# Tiny_Programmer_v10.net
KiCad netlist of a schematic drawn in EAGLE
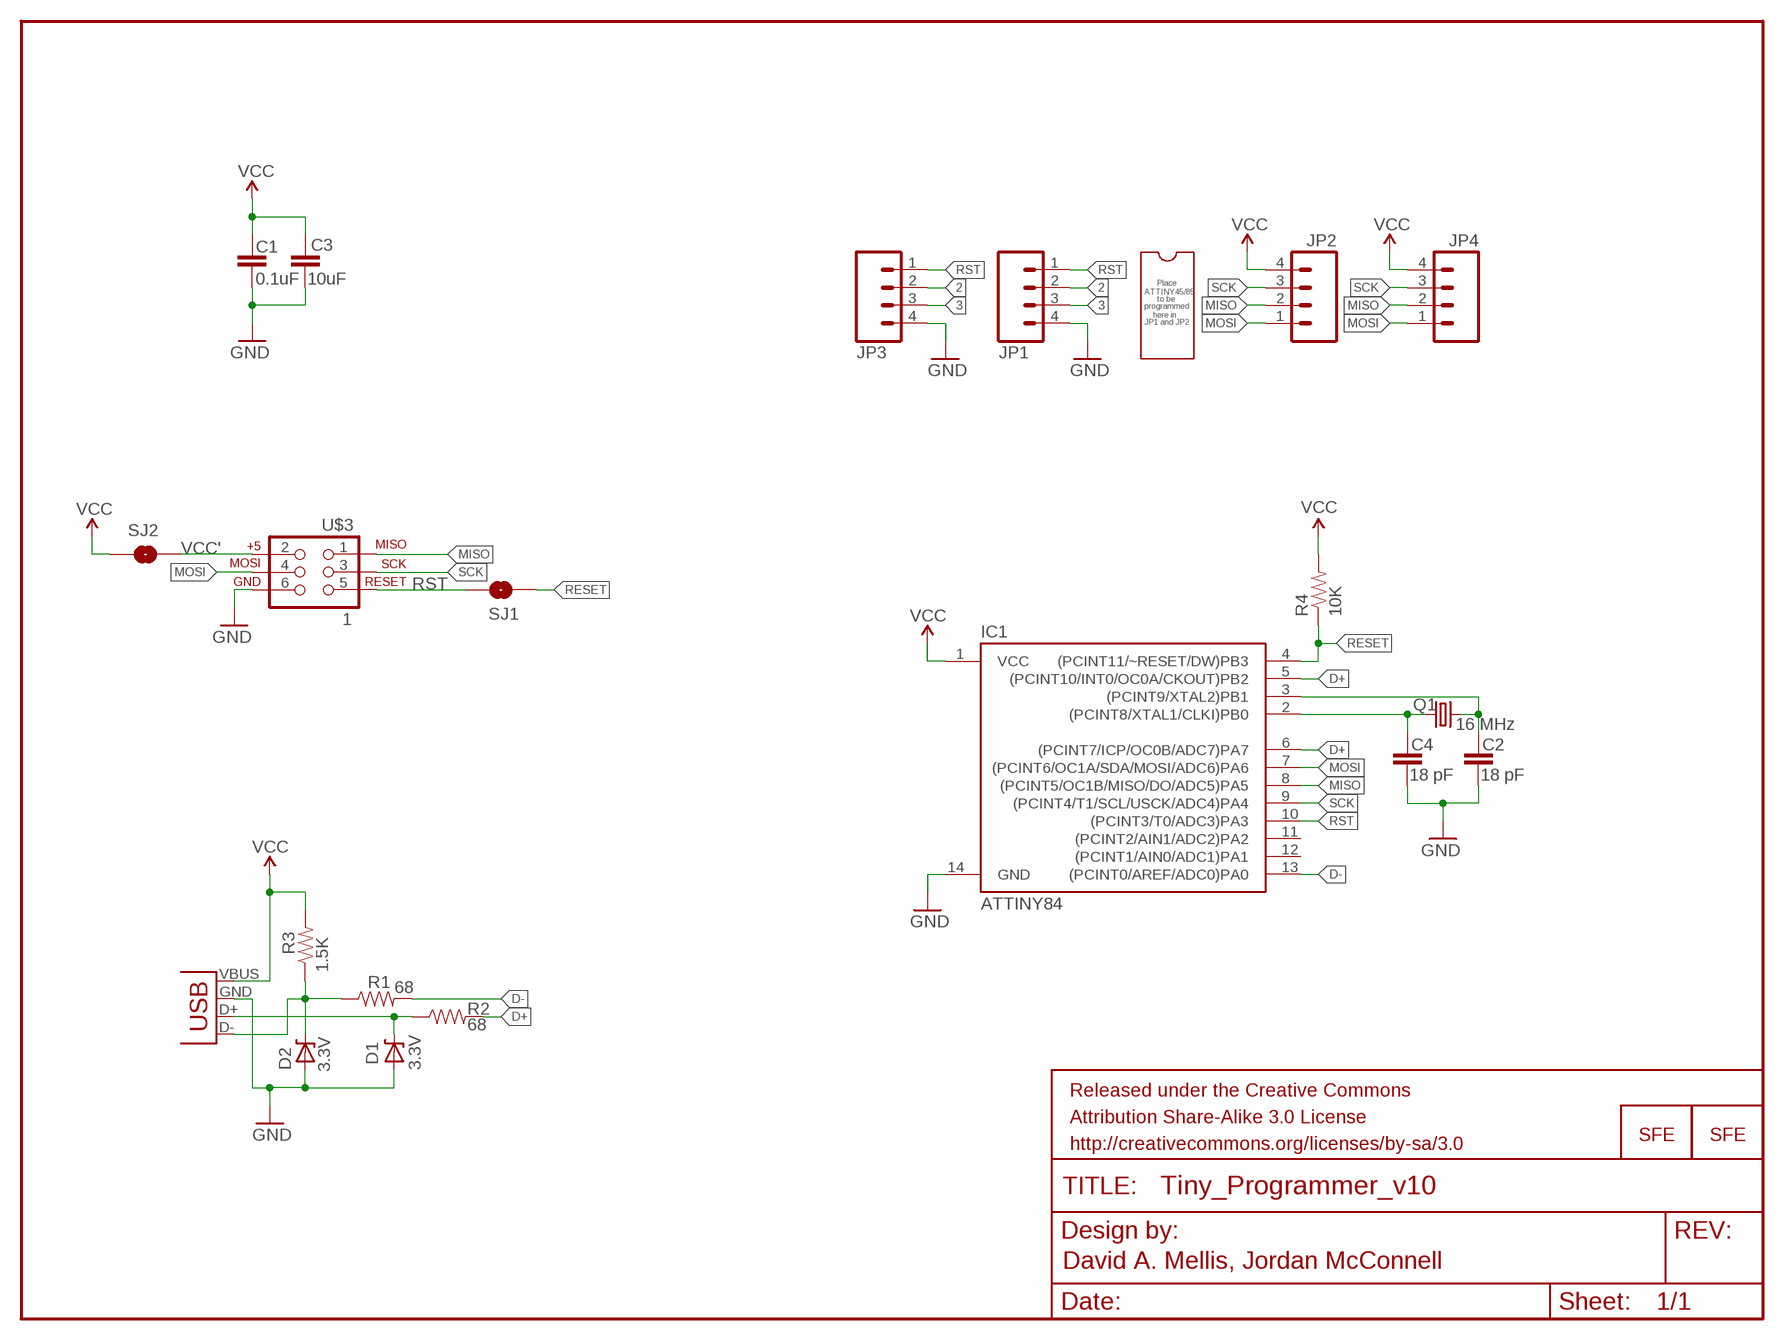
[diagram p0: schematic, sheet 1]

(export (version "E")
  (design (tool "Eeschema 10.0.6"))
  (components
    (comp (ref "C1")
      (value "0.1uF")
      (footprint "eagle-import:0402-CAP")
      (libsource (lib "eagle-import") (part "CAP0402-CAP"))
    )
    (comp (ref "C2")
      (value "18 pF")
      (footprint "eagle-import:0402-CAP")
      (libsource (lib "eagle-import") (part "CAP0402-CAP"))
    )
    (comp (ref "C3")
      (value "10uF")
      (footprint "eagle-import:0402-CAP")
      (libsource (lib "eagle-import") (part "CAP0402-CAP"))
    )
    (comp (ref "C4")
      (value "18 pF")
      (footprint "eagle-import:0402-CAP")
      (libsource (lib "eagle-import") (part "CAP0402-CAP"))
    )
    (comp (ref "D1")
      (value "3.3V")
      (footprint "eagle-import:SOD-323")
      (libsource (lib "eagle-import") (part "DIODE-ZENER-BZT52"))
    )
    (comp (ref "D2")
      (value "3.3V")
      (footprint "eagle-import:SOD-323")
      (libsource (lib "eagle-import") (part "DIODE-ZENER-BZT52"))
    )
    (comp (ref "FRAME1")
      (value "FRAME-LETTER")
      (footprint "eagle-import:CREATIVE_COMMONS")
      (libsource (lib "eagle-import") (part "FRAME-LETTER"))
    )
    (comp (ref "IC1")
      (value "ATTINY84")
      (footprint "eagle-import:SO14")
      (libsource (lib "eagle-import") (part "ATTINY84"))
    )
    (comp (ref "JP1")
      (value "M04SMD_STRAIGHT_COMBO")
      (footprint "eagle-import:1X04_SMD_STRAIGHT_COMBO")
      (libsource (lib "eagle-import") (part "M04SMD_STRAIGHT_COMBO"))
    )
    (comp (ref "JP2")
      (value "M04SMD_STRAIGHT_COMBO")
      (footprint "eagle-import:1X04_SMD_STRAIGHT_COMBO")
      (libsource (lib "eagle-import") (part "M04SMD_STRAIGHT_COMBO"))
    )
    (comp (ref "JP3")
      (value "M04SMD_STRAIGHT_COMBO")
      (footprint "eagle-import:1X04_SMD_STRAIGHT_COMBO")
      (libsource (lib "eagle-import") (part "M04SMD_STRAIGHT_COMBO"))
    )
    (comp (ref "JP4")
      (value "M04SMD_STRAIGHT_COMBO")
      (footprint "eagle-import:1X04_SMD_STRAIGHT_COMBO")
      (libsource (lib "eagle-import") (part "M04SMD_STRAIGHT_COMBO"))
    )
    (comp (ref "JP5")
      (value "LOGO-SFENEW")
      (footprint "eagle-import:SFE-NEW-WEBLOGO")
      (libsource (lib "eagle-import") (part "LOGO-SFENEW"))
    )
    (comp (ref "JP6")
      (value "LOGO-SFESK")
      (footprint "eagle-import:SFE-LOGO-FLAME")
      (libsource (lib "eagle-import") (part "LOGO-SFESK"))
    )
    (comp (ref "Q1")
      (value "16 MHz")
      (footprint "eagle-import:CRYSTAL-SMD-5X3")
      (libsource (lib "eagle-import") (part "CRYSTAL5X3"))
    )
    (comp (ref "R1")
      (value "68")
      (footprint "eagle-import:0402-RES")
      (libsource (lib "eagle-import") (part "RESISTOR0402-RES"))
    )
    (comp (ref "R2")
      (value "68")
      (footprint "eagle-import:0402-RES")
      (libsource (lib "eagle-import") (part "RESISTOR0402-RES"))
    )
    (comp (ref "R3")
      (value "1.5K")
      (footprint "eagle-import:0402-RES")
      (libsource (lib "eagle-import") (part "RESISTOR0402-RES"))
    )
    (comp (ref "R4")
      (value "10K")
      (footprint "eagle-import:0402-RES")
      (libsource (lib "eagle-import") (part "RESISTOR0402-RES"))
    )
    (comp (ref "SJ1")
      (value "SOLDERJUMPERNO")
      (footprint "eagle-import:SJ_2S-NO")
      (libsource (lib "eagle-import") (part "SOLDERJUMPERNO"))
    )
    (comp (ref "SJ2")
      (value "SOLDERJUMPERNO")
      (footprint "eagle-import:SJ_2S-NO")
      (libsource (lib "eagle-import") (part "SOLDERJUMPERNO"))
    )
    (comp (ref "U$3")
      (value "1")
      (footprint "eagle-import:2X3")
      (libsource (lib "eagle-import") (part "AVR_SPI_PRG_6PTH"))
    )
    (comp (ref "X1")
      (value "USB-A-H")
      (footprint "eagle-import:USB-A-H")
      (libsource (lib "eagle-import") (part "USB-A-H"))
    )
  )
  (nets
    (net (code "1") (name "/VCC'") (class "Default")
      (node (ref "SJ2") (pin "2") (pinfunction "2_2") (pintype "passive"))
      (node (ref "U$3") (pin "2") (pinfunction "2_2") (pintype "passive"))
    )
    (net (code "2") (name "2") (class "Default")
      (node (ref "JP1") (pin "2") (pinfunction "2_2") (pintype "passive"))
      (node (ref "JP3") (pin "2") (pinfunction "2_2") (pintype "passive"))
    )
    (net (code "3") (name "3") (class "Default")
      (node (ref "JP1") (pin "3") (pinfunction "3_3") (pintype "passive"))
      (node (ref "JP3") (pin "3") (pinfunction "3_3") (pintype "passive"))
    )
    (net (code "4") (name "D+") (class "Default")
      (node (ref "IC1") (pin "5") (pinfunction "(PCINT10/INT0/OC0A/CKOUT)PB2_5") (pintype "bidirectional"))
      (node (ref "IC1") (pin "6") (pinfunction "(PCINT7/ICP/OC0B/ADC7)PA7_6") (pintype "bidirectional"))
      (node (ref "R2") (pin "2") (pinfunction "2_2") (pintype "passive"))
    )
    (net (code "5") (name "D-") (class "Default")
      (node (ref "IC1") (pin "13") (pinfunction "(PCINT0/AREF/ADC0)PA0_13") (pintype "bidirectional"))
      (node (ref "R1") (pin "2") (pinfunction "2_2") (pintype "passive"))
    )
    (net (code "6") (name "GND") (class "Default")
      (node (ref "C1") (pin "2") (pinfunction "2_2") (pintype "passive"))
      (node (ref "C2") (pin "2") (pinfunction "2_2") (pintype "passive"))
      (node (ref "C3") (pin "2") (pinfunction "2_2") (pintype "passive"))
      (node (ref "C4") (pin "2") (pinfunction "2_2") (pintype "passive"))
      (node (ref "D1") (pin "2") (pinfunction "A_2") (pintype "passive"))
      (node (ref "D2") (pin "2") (pinfunction "A_2") (pintype "passive"))
      (node (ref "IC1") (pin "14") (pinfunction "GND_14") (pintype "bidirectional"))
      (node (ref "JP1") (pin "4") (pinfunction "4_4") (pintype "passive"))
      (node (ref "JP3") (pin "4") (pinfunction "4_4") (pintype "passive"))
      (node (ref "U$3") (pin "6") (pinfunction "6_6") (pintype "passive"))
      (node (ref "X1") (pin "GND") (pinfunction "VBUS_GND") (pintype "bidirectional"))
    )
    (net (code "7") (name "MISO") (class "Default")
      (node (ref "IC1") (pin "8") (pinfunction "(PCINT5/OC1B/MISO/DO/ADC5)PA5_8") (pintype "bidirectional"))
      (node (ref "JP2") (pin "2") (pinfunction "2_2") (pintype "passive"))
      (node (ref "JP4") (pin "2") (pinfunction "2_2") (pintype "passive"))
      (node (ref "U$3") (pin "1") (pinfunction "1_1") (pintype "passive"))
    )
    (net (code "8") (name "MOSI") (class "Default")
      (node (ref "IC1") (pin "7") (pinfunction "(PCINT6/OC1A/SDA/MOSI/ADC6)PA6_7") (pintype "bidirectional"))
      (node (ref "JP2") (pin "1") (pinfunction "1_1") (pintype "passive"))
      (node (ref "JP4") (pin "1") (pinfunction "1_1") (pintype "passive"))
      (node (ref "U$3") (pin "4") (pinfunction "4_4") (pintype "passive"))
    )
    (net (code "9") (name "Net-(D1-C)") (class "Default")
      (node (ref "D1") (pin "1") (pinfunction "C_1") (pintype "passive"))
      (node (ref "R2") (pin "1") (pinfunction "1_1") (pintype "passive"))
      (node (ref "X1") (pin "D+") (pinfunction "D-_D+") (pintype "bidirectional"))
    )
    (net (code "10") (name "Net-(D2-C)") (class "Default")
      (node (ref "D2") (pin "1") (pinfunction "C_1") (pintype "passive"))
      (node (ref "R1") (pin "1") (pinfunction "1_1") (pintype "passive"))
      (node (ref "R3") (pin "1") (pinfunction "1_1") (pintype "passive"))
      (node (ref "X1") (pin "D-") (pinfunction "D+_D-") (pintype "bidirectional"))
    )
    (net (code "11") (name "Net-(IC1-(PCINT8{slash}XTAL1{slash}CLKI)PB0)") (class "Default")
      (node (ref "C4") (pin "1") (pinfunction "1_1") (pintype "passive"))
      (node (ref "IC1") (pin "2") (pinfunction "(PCINT8/XTAL1/CLKI)PB0_2") (pintype "bidirectional"))
      (node (ref "Q1") (pin "1") (pinfunction "1_1") (pintype "passive"))
    )
    (net (code "12") (name "Net-(IC1-(PCINT9{slash}XTAL2)PB1)") (class "Default")
      (node (ref "C2") (pin "1") (pinfunction "1_1") (pintype "passive"))
      (node (ref "IC1") (pin "3") (pinfunction "(PCINT9/XTAL2)PB1_3") (pintype "bidirectional"))
      (node (ref "Q1") (pin "3") (pinfunction "2_3") (pintype "passive"))
    )
    (net (code "13") (name "RESET") (class "Default")
      (node (ref "IC1") (pin "4") (pinfunction "(PCINT11/~{RESET/DW})PB3_4") (pintype "bidirectional"))
      (node (ref "R4") (pin "1") (pinfunction "1_1") (pintype "passive"))
      (node (ref "SJ1") (pin "1") (pinfunction "1_1") (pintype "passive"))
    )
    (net (code "14") (name "RST") (class "Default")
      (node (ref "IC1") (pin "10") (pinfunction "(PCINT3/T0/ADC3)PA3_10") (pintype "bidirectional"))
      (node (ref "JP1") (pin "1") (pinfunction "1_1") (pintype "passive"))
      (node (ref "JP3") (pin "1") (pinfunction "1_1") (pintype "passive"))
      (node (ref "SJ1") (pin "2") (pinfunction "2_2") (pintype "passive"))
      (node (ref "U$3") (pin "5") (pinfunction "5_5") (pintype "passive"))
    )
    (net (code "15") (name "SCK") (class "Default")
      (node (ref "IC1") (pin "9") (pinfunction "(PCINT4/T1/SCL/USCK/ADC4)PA4_9") (pintype "bidirectional"))
      (node (ref "JP2") (pin "3") (pinfunction "3_3") (pintype "passive"))
      (node (ref "JP4") (pin "3") (pinfunction "3_3") (pintype "passive"))
      (node (ref "U$3") (pin "3") (pinfunction "3_3") (pintype "passive"))
    )
    (net (code "16") (name "VCC") (class "Default")
      (node (ref "C1") (pin "1") (pinfunction "1_1") (pintype "passive"))
      (node (ref "C3") (pin "1") (pinfunction "1_1") (pintype "passive"))
      (node (ref "IC1") (pin "1") (pinfunction "VCC_1") (pintype "bidirectional"))
      (node (ref "JP2") (pin "4") (pinfunction "4_4") (pintype "passive"))
      (node (ref "JP4") (pin "4") (pinfunction "4_4") (pintype "passive"))
      (node (ref "R3") (pin "2") (pinfunction "2_2") (pintype "passive"))
      (node (ref "R4") (pin "2") (pinfunction "2_2") (pintype "passive"))
      (node (ref "SJ2") (pin "1") (pinfunction "1_1") (pintype "passive"))
      (node (ref "X1") (pin "VBUS") (pinfunction "GND_VBUS") (pintype "bidirectional"))
    )
    (net (code "17") (name "unconnected-(IC1-(PCINT1{slash}AIN0{slash}ADC1)PA1-Pad12)") (class "Default")
      (node (ref "IC1") (pin "12") (pinfunction "(PCINT1/AIN0/ADC1)PA1_12") (pintype "bidirectional"))
    )
    (net (code "18") (name "unconnected-(IC1-(PCINT2{slash}AIN1{slash}ADC2)PA2-Pad11)") (class "Default")
      (node (ref "IC1") (pin "11") (pinfunction "(PCINT2/AIN1/ADC2)PA2_11") (pintype "bidirectional"))
    )
  )
)
